# LEDBOARD_v1.net
KiCad netlist of a schematic drawn in EAGLE
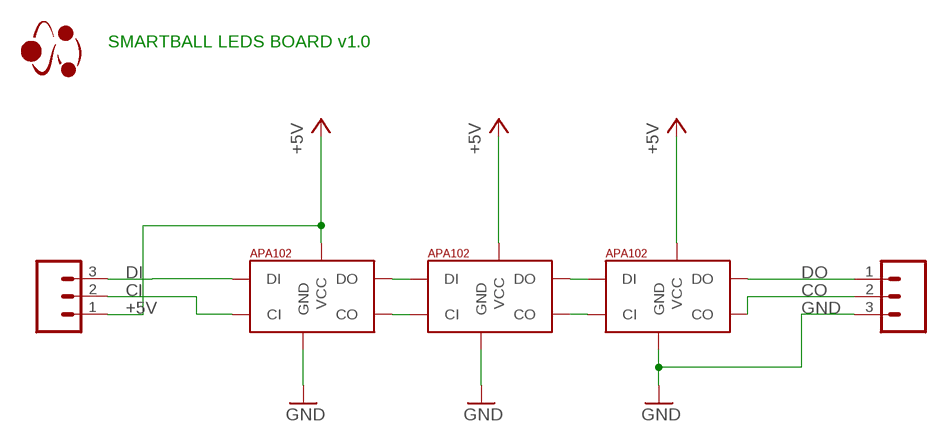
[diagram p0: schematic, sheet 1]

(export (version "E")
  (design (tool "Eeschema 10.0.6"))
  (components
    (comp (ref "U$1")
      (value "APA102")
      (footprint "eagle-import:APA102_5050_SB")
      (libsource (lib "eagle-import") (part "APA102"))
    )
    (comp (ref "U$2")
      (value "APA102")
      (footprint "eagle-import:APA102_5050_SB")
      (libsource (lib "eagle-import") (part "APA102"))
    )
    (comp (ref "U$3")
      (value "APA102")
      (footprint "eagle-import:APA102_5050_SB")
      (libsource (lib "eagle-import") (part "APA102"))
    )
    (comp (ref "U$4")
      (value "LOGO_SMARTBALL")
      (footprint "eagle-import:SMARTBALL_LOGO")
      (libsource (lib "eagle-import") (part "LOGO_SMARTBALL"))
    )
    (comp (ref "U$5")
      (value "CONN_03_SMDCONN03_SMD_MALE")
      (footprint "eagle-import:CONN03_SMD_MALE")
      (libsource (lib "eagle-import") (part "CONN_03_SMDCONN03_SMD_MALE"))
    )
    (comp (ref "U$6")
      (value "CONN_03_SMDCONN03_SMD_MALE")
      (footprint "eagle-import:CONN03_SMD_MALE")
      (libsource (lib "eagle-import") (part "CONN_03_SMDCONN03_SMD_MALE"))
    )
  )
  (nets
    (net (code "1") (name "+5V") (class "Default")
      (node (ref "U$1") (pin "VCC") (pinfunction "VCC_VCC") (pintype "bidirectional"))
      (node (ref "U$2") (pin "VCC") (pinfunction "VCC_VCC") (pintype "bidirectional"))
      (node (ref "U$3") (pin "VCC") (pinfunction "VCC_VCC") (pintype "bidirectional"))
      (node (ref "U$5") (pin "1") (pinfunction "1_1") (pintype "passive"))
    )
    (net (code "2") (name "/CI") (class "Default")
      (node (ref "U$1") (pin "CI") (pinfunction "CI_CI") (pintype "bidirectional"))
      (node (ref "U$1") (pin "CI2") (pinfunction "CI_CI2") (pintype "bidirectional"))
      (node (ref "U$5") (pin "2") (pinfunction "2_2") (pintype "passive"))
    )
    (net (code "3") (name "/CO") (class "Default")
      (node (ref "U$3") (pin "CO") (pinfunction "CO_CO") (pintype "bidirectional"))
      (node (ref "U$6") (pin "2") (pinfunction "2_2") (pintype "passive"))
    )
    (net (code "4") (name "/DI") (class "Default")
      (node (ref "U$1") (pin "DI") (pinfunction "DI_DI") (pintype "bidirectional"))
      (node (ref "U$1") (pin "DI2") (pinfunction "DI_DI2") (pintype "bidirectional"))
      (node (ref "U$5") (pin "3") (pinfunction "3_3") (pintype "passive"))
    )
    (net (code "5") (name "/DO") (class "Default")
      (node (ref "U$3") (pin "DO") (pinfunction "DO_DO") (pintype "bidirectional"))
      (node (ref "U$6") (pin "1") (pinfunction "1_1") (pintype "passive"))
    )
    (net (code "6") (name "GND") (class "Default")
      (node (ref "U$1") (pin "GND") (pinfunction "GND_GND") (pintype "bidirectional"))
      (node (ref "U$1") (pin "GND2") (pinfunction "GND_GND2") (pintype "bidirectional"))
      (node (ref "U$2") (pin "GND") (pinfunction "GND_GND") (pintype "bidirectional"))
      (node (ref "U$2") (pin "GND2") (pinfunction "GND_GND2") (pintype "bidirectional"))
      (node (ref "U$3") (pin "GND") (pinfunction "GND_GND") (pintype "bidirectional"))
      (node (ref "U$3") (pin "GND2") (pinfunction "GND_GND2") (pintype "bidirectional"))
      (node (ref "U$6") (pin "3") (pinfunction "3_3") (pintype "passive"))
    )
    (net (code "7") (name "Net-(U$1-PadCO)") (class "Default")
      (node (ref "U$1") (pin "CO") (pinfunction "CO_CO") (pintype "bidirectional"))
      (node (ref "U$2") (pin "CI") (pinfunction "CI_CI") (pintype "bidirectional"))
      (node (ref "U$2") (pin "CI2") (pinfunction "CI_CI2") (pintype "bidirectional"))
    )
    (net (code "8") (name "Net-(U$1-PadDO)") (class "Default")
      (node (ref "U$1") (pin "DO") (pinfunction "DO_DO") (pintype "bidirectional"))
      (node (ref "U$2") (pin "DI") (pinfunction "DI_DI") (pintype "bidirectional"))
      (node (ref "U$2") (pin "DI2") (pinfunction "DI_DI2") (pintype "bidirectional"))
    )
    (net (code "9") (name "Net-(U$2-PadCO)") (class "Default")
      (node (ref "U$2") (pin "CO") (pinfunction "CO_CO") (pintype "bidirectional"))
      (node (ref "U$3") (pin "CI") (pinfunction "CI_CI") (pintype "bidirectional"))
      (node (ref "U$3") (pin "CI2") (pinfunction "CI_CI2") (pintype "bidirectional"))
    )
    (net (code "10") (name "Net-(U$2-PadDO)") (class "Default")
      (node (ref "U$2") (pin "DO") (pinfunction "DO_DO") (pintype "bidirectional"))
      (node (ref "U$3") (pin "DI") (pinfunction "DI_DI") (pintype "bidirectional"))
      (node (ref "U$3") (pin "DI2") (pinfunction "DI_DI2") (pintype "bidirectional"))
    )
  )
)
